# breakout.net
KiCad netlist of a schematic drawn in EAGLE
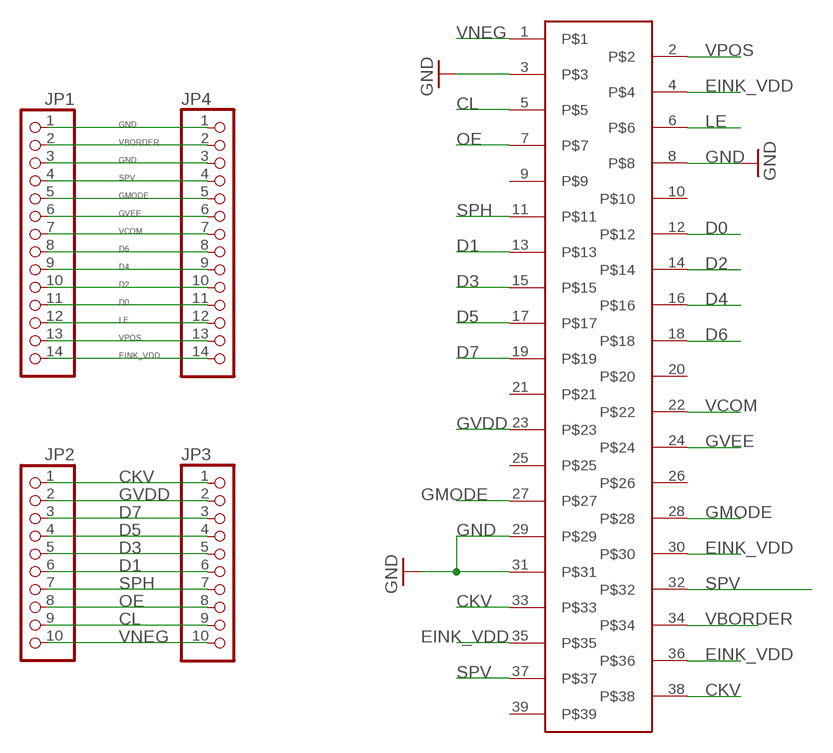
[diagram p0: schematic, sheet 1]

(export (version "E")
  (design (tool "Eeschema 10.0.6"))
  (components
    (comp (ref "JP1")
      (value "PINHD-1X14")
      (footprint "eagle-import:1X14")
      (libsource (lib "eagle-import") (part "PINHD-1X14"))
    )
    (comp (ref "JP2")
      (value "PINHD-1X10")
      (footprint "eagle-import:1X10")
      (libsource (lib "eagle-import") (part "PINHD-1X10"))
    )
    (comp (ref "JP3")
      (value "PINHD-1X10")
      (footprint "eagle-import:1X10")
      (libsource (lib "eagle-import") (part "PINHD-1X10"))
    )
    (comp (ref "JP4")
      (value "PINHD-1X14")
      (footprint "eagle-import:1X14")
      (libsource (lib "eagle-import") (part "PINHD-1X14"))
    )
    (comp (ref "U$1")
      (value "JCT-39")
      (footprint "eagle-import:JCT-39")
      (libsource (lib "eagle-import") (part "JCT-39"))
    )
  )
  (nets
    (net (code "1") (name "/CKV") (class "Default")
      (node (ref "JP2") (pin "1") (pinfunction "1_1") (pintype "passive"))
      (node (ref "JP3") (pin "1") (pinfunction "1_1") (pintype "passive"))
      (node (ref "U$1") (pin "33") (pinfunction "P$33_33") (pintype "bidirectional"))
      (node (ref "U$1") (pin "38") (pinfunction "P$38_38") (pintype "bidirectional"))
    )
    (net (code "2") (name "/CL") (class "Default")
      (node (ref "JP2") (pin "9") (pinfunction "9_9") (pintype "passive"))
      (node (ref "JP3") (pin "9") (pinfunction "9_9") (pintype "passive"))
      (node (ref "U$1") (pin "5") (pinfunction "P$5_5") (pintype "bidirectional"))
    )
    (net (code "3") (name "/D0") (class "Default")
      (node (ref "JP1") (pin "11") (pinfunction "11_11") (pintype "passive"))
      (node (ref "JP4") (pin "11") (pinfunction "11_11") (pintype "passive"))
      (node (ref "U$1") (pin "12") (pinfunction "P$12_12") (pintype "bidirectional"))
    )
    (net (code "4") (name "/D1") (class "Default")
      (node (ref "JP2") (pin "6") (pinfunction "6_6") (pintype "passive"))
      (node (ref "JP3") (pin "6") (pinfunction "6_6") (pintype "passive"))
      (node (ref "U$1") (pin "13") (pinfunction "P$13_13") (pintype "bidirectional"))
    )
    (net (code "5") (name "/D2") (class "Default")
      (node (ref "JP1") (pin "10") (pinfunction "10_10") (pintype "passive"))
      (node (ref "JP4") (pin "10") (pinfunction "10_10") (pintype "passive"))
      (node (ref "U$1") (pin "14") (pinfunction "P$14_14") (pintype "bidirectional"))
    )
    (net (code "6") (name "/D3") (class "Default")
      (node (ref "JP2") (pin "5") (pinfunction "5_5") (pintype "passive"))
      (node (ref "JP3") (pin "5") (pinfunction "5_5") (pintype "passive"))
      (node (ref "U$1") (pin "15") (pinfunction "P$15_15") (pintype "bidirectional"))
    )
    (net (code "7") (name "/D4") (class "Default")
      (node (ref "JP1") (pin "9") (pinfunction "9_9") (pintype "passive"))
      (node (ref "JP4") (pin "9") (pinfunction "9_9") (pintype "passive"))
      (node (ref "U$1") (pin "16") (pinfunction "P$16_16") (pintype "bidirectional"))
    )
    (net (code "8") (name "/D5") (class "Default")
      (node (ref "JP2") (pin "4") (pinfunction "4_4") (pintype "passive"))
      (node (ref "JP3") (pin "4") (pinfunction "4_4") (pintype "passive"))
      (node (ref "U$1") (pin "17") (pinfunction "P$17_17") (pintype "bidirectional"))
    )
    (net (code "9") (name "/D6") (class "Default")
      (node (ref "JP1") (pin "8") (pinfunction "8_8") (pintype "passive"))
      (node (ref "JP4") (pin "8") (pinfunction "8_8") (pintype "passive"))
      (node (ref "U$1") (pin "18") (pinfunction "P$18_18") (pintype "bidirectional"))
    )
    (net (code "10") (name "/D7") (class "Default")
      (node (ref "JP2") (pin "3") (pinfunction "3_3") (pintype "passive"))
      (node (ref "JP3") (pin "3") (pinfunction "3_3") (pintype "passive"))
      (node (ref "U$1") (pin "19") (pinfunction "P$19_19") (pintype "bidirectional"))
    )
    (net (code "11") (name "/EINK_VDD") (class "Default")
      (node (ref "JP1") (pin "14") (pinfunction "14_14") (pintype "passive"))
      (node (ref "JP4") (pin "14") (pinfunction "14_14") (pintype "passive"))
      (node (ref "U$1") (pin "30") (pinfunction "P$30_30") (pintype "bidirectional"))
      (node (ref "U$1") (pin "35") (pinfunction "P$35_35") (pintype "bidirectional"))
      (node (ref "U$1") (pin "36") (pinfunction "P$36_36") (pintype "bidirectional"))
      (node (ref "U$1") (pin "4") (pinfunction "P$4_4") (pintype "bidirectional"))
    )
    (net (code "12") (name "/GMODE") (class "Default")
      (node (ref "JP1") (pin "5") (pinfunction "5_5") (pintype "passive"))
      (node (ref "JP4") (pin "5") (pinfunction "5_5") (pintype "passive"))
      (node (ref "U$1") (pin "27") (pinfunction "P$27_27") (pintype "bidirectional"))
      (node (ref "U$1") (pin "28") (pinfunction "P$28_28") (pintype "bidirectional"))
    )
    (net (code "13") (name "/GVDD") (class "Default")
      (node (ref "JP2") (pin "2") (pinfunction "2_2") (pintype "passive"))
      (node (ref "JP3") (pin "2") (pinfunction "2_2") (pintype "passive"))
      (node (ref "U$1") (pin "23") (pinfunction "P$23_23") (pintype "bidirectional"))
    )
    (net (code "14") (name "/GVEE") (class "Default")
      (node (ref "JP1") (pin "6") (pinfunction "6_6") (pintype "passive"))
      (node (ref "JP4") (pin "6") (pinfunction "6_6") (pintype "passive"))
      (node (ref "U$1") (pin "24") (pinfunction "P$24_24") (pintype "bidirectional"))
    )
    (net (code "15") (name "/LE") (class "Default")
      (node (ref "JP1") (pin "12") (pinfunction "12_12") (pintype "passive"))
      (node (ref "JP4") (pin "12") (pinfunction "12_12") (pintype "passive"))
      (node (ref "U$1") (pin "6") (pinfunction "P$6_6") (pintype "bidirectional"))
    )
    (net (code "16") (name "/OE") (class "Default")
      (node (ref "JP2") (pin "8") (pinfunction "8_8") (pintype "passive"))
      (node (ref "JP3") (pin "8") (pinfunction "8_8") (pintype "passive"))
      (node (ref "U$1") (pin "7") (pinfunction "P$7_7") (pintype "bidirectional"))
    )
    (net (code "17") (name "/SPH") (class "Default")
      (node (ref "JP2") (pin "7") (pinfunction "7_7") (pintype "passive"))
      (node (ref "JP3") (pin "7") (pinfunction "7_7") (pintype "passive"))
      (node (ref "U$1") (pin "11") (pinfunction "P$11_11") (pintype "bidirectional"))
    )
    (net (code "18") (name "/SPV") (class "Default")
      (node (ref "JP1") (pin "4") (pinfunction "4_4") (pintype "passive"))
      (node (ref "JP4") (pin "4") (pinfunction "4_4") (pintype "passive"))
      (node (ref "U$1") (pin "32") (pinfunction "P$32_32") (pintype "bidirectional"))
      (node (ref "U$1") (pin "37") (pinfunction "P$37_37") (pintype "bidirectional"))
    )
    (net (code "19") (name "/VBORDER") (class "Default")
      (node (ref "JP1") (pin "2") (pinfunction "2_2") (pintype "passive"))
      (node (ref "JP4") (pin "2") (pinfunction "2_2") (pintype "passive"))
      (node (ref "U$1") (pin "34") (pinfunction "P$34_34") (pintype "bidirectional"))
    )
    (net (code "20") (name "/VCOM") (class "Default")
      (node (ref "JP1") (pin "7") (pinfunction "7_7") (pintype "passive"))
      (node (ref "JP4") (pin "7") (pinfunction "7_7") (pintype "passive"))
      (node (ref "U$1") (pin "22") (pinfunction "P$22_22") (pintype "bidirectional"))
    )
    (net (code "21") (name "/VNEG") (class "Default")
      (node (ref "JP2") (pin "10") (pinfunction "10_10") (pintype "passive"))
      (node (ref "JP3") (pin "10") (pinfunction "10_10") (pintype "passive"))
      (node (ref "U$1") (pin "1") (pinfunction "P$1_1") (pintype "bidirectional"))
    )
    (net (code "22") (name "/VPOS") (class "Default")
      (node (ref "JP1") (pin "13") (pinfunction "13_13") (pintype "passive"))
      (node (ref "JP4") (pin "13") (pinfunction "13_13") (pintype "passive"))
      (node (ref "U$1") (pin "2") (pinfunction "P$2_2") (pintype "bidirectional"))
    )
    (net (code "23") (name "GND") (class "Default")
      (node (ref "JP1") (pin "1") (pinfunction "1_1") (pintype "passive"))
      (node (ref "JP1") (pin "3") (pinfunction "3_3") (pintype "passive"))
      (node (ref "JP4") (pin "1") (pinfunction "1_1") (pintype "passive"))
      (node (ref "JP4") (pin "3") (pinfunction "3_3") (pintype "passive"))
      (node (ref "U$1") (pin "29") (pinfunction "P$29_29") (pintype "bidirectional"))
      (node (ref "U$1") (pin "3") (pinfunction "P$3_3") (pintype "bidirectional"))
      (node (ref "U$1") (pin "31") (pinfunction "P$31_31") (pintype "bidirectional"))
      (node (ref "U$1") (pin "8") (pinfunction "P$8_8") (pintype "bidirectional"))
    )
    (net (code "24") (name "unconnected-(U$1-P$9-Pad9)") (class "Default")
      (node (ref "U$1") (pin "9") (pinfunction "P$9_9") (pintype "bidirectional"))
    )
    (net (code "25") (name "unconnected-(U$1-P$10-Pad10)") (class "Default")
      (node (ref "U$1") (pin "10") (pinfunction "P$10_10") (pintype "bidirectional"))
    )
    (net (code "26") (name "unconnected-(U$1-P$20-Pad20)") (class "Default")
      (node (ref "U$1") (pin "20") (pinfunction "P$20_20") (pintype "bidirectional"))
    )
    (net (code "27") (name "unconnected-(U$1-P$21-Pad21)") (class "Default")
      (node (ref "U$1") (pin "21") (pinfunction "P$21_21") (pintype "bidirectional"))
    )
    (net (code "28") (name "unconnected-(U$1-P$25-Pad25)") (class "Default")
      (node (ref "U$1") (pin "25") (pinfunction "P$25_25") (pintype "bidirectional"))
    )
    (net (code "29") (name "unconnected-(U$1-P$26-Pad26)") (class "Default")
      (node (ref "U$1") (pin "26") (pinfunction "P$26_26") (pintype "bidirectional"))
    )
    (net (code "30") (name "unconnected-(U$1-P$39-Pad39)") (class "Default")
      (node (ref "U$1") (pin "39") (pinfunction "P$39_39") (pintype "bidirectional"))
    )
  )
)
